# SOT-23-5.net
KiCad netlist of a schematic drawn in EAGLE
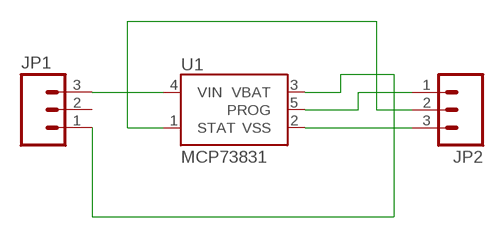
[diagram p0: schematic, sheet 1]

(export (version "E")
  (design (tool "Eeschema 10.0.6"))
  (components
    (comp (ref "JP1")
      (value "M03LOCK")
      (footprint "eagle-import:1X03_LOCK")
      (libsource (lib "eagle-import") (part "M03LOCK"))
    )
    (comp (ref "JP2")
      (value "M03LOCK")
      (footprint "eagle-import:1X03_LOCK")
      (libsource (lib "eagle-import") (part "M03LOCK"))
    )
    (comp (ref "U1")
      (value "MCP73831")
      (footprint "eagle-import:SOT23-5")
      (libsource (lib "eagle-import") (part "MCP73831"))
    )
  )
  (nets
    (net (code "1") (name "Net-(U1-PROG)") (class "Default")
      (node (ref "JP2") (pin "1") (pinfunction "1_1") (pintype "passive"))
      (node (ref "U1") (pin "5") (pinfunction "PROG_5") (pintype "input"))
    )
    (net (code "2") (name "Net-(U1-STAT)") (class "Default")
      (node (ref "JP2") (pin "2") (pinfunction "2_2") (pintype "passive"))
      (node (ref "U1") (pin "1") (pinfunction "STAT_1") (pintype "output"))
    )
    (net (code "3") (name "Net-(U1-VBAT)") (class "Default")
      (node (ref "JP1") (pin "1") (pinfunction "1_1") (pintype "passive"))
      (node (ref "U1") (pin "3") (pinfunction "VBAT_3") (pintype "power_in"))
    )
    (net (code "4") (name "Net-(U1-VIN)") (class "Default")
      (node (ref "JP1") (pin "3") (pinfunction "3_3") (pintype "passive"))
      (node (ref "U1") (pin "4") (pinfunction "VIN_4") (pintype "power_in"))
    )
    (net (code "5") (name "Net-(U1-VSS)") (class "Default")
      (node (ref "JP2") (pin "3") (pinfunction "3_3") (pintype "passive"))
      (node (ref "U1") (pin "2") (pinfunction "VSS_2") (pintype "power_in"))
    )
    (net (code "6") (name "unconnected-(JP1-Pad2)") (class "Default")
      (node (ref "JP1") (pin "2") (pinfunction "2_2") (pintype "passive"))
    )
  )
)
